# Main_System.net
KiCad netlist of a schematic drawn in Altium Designer
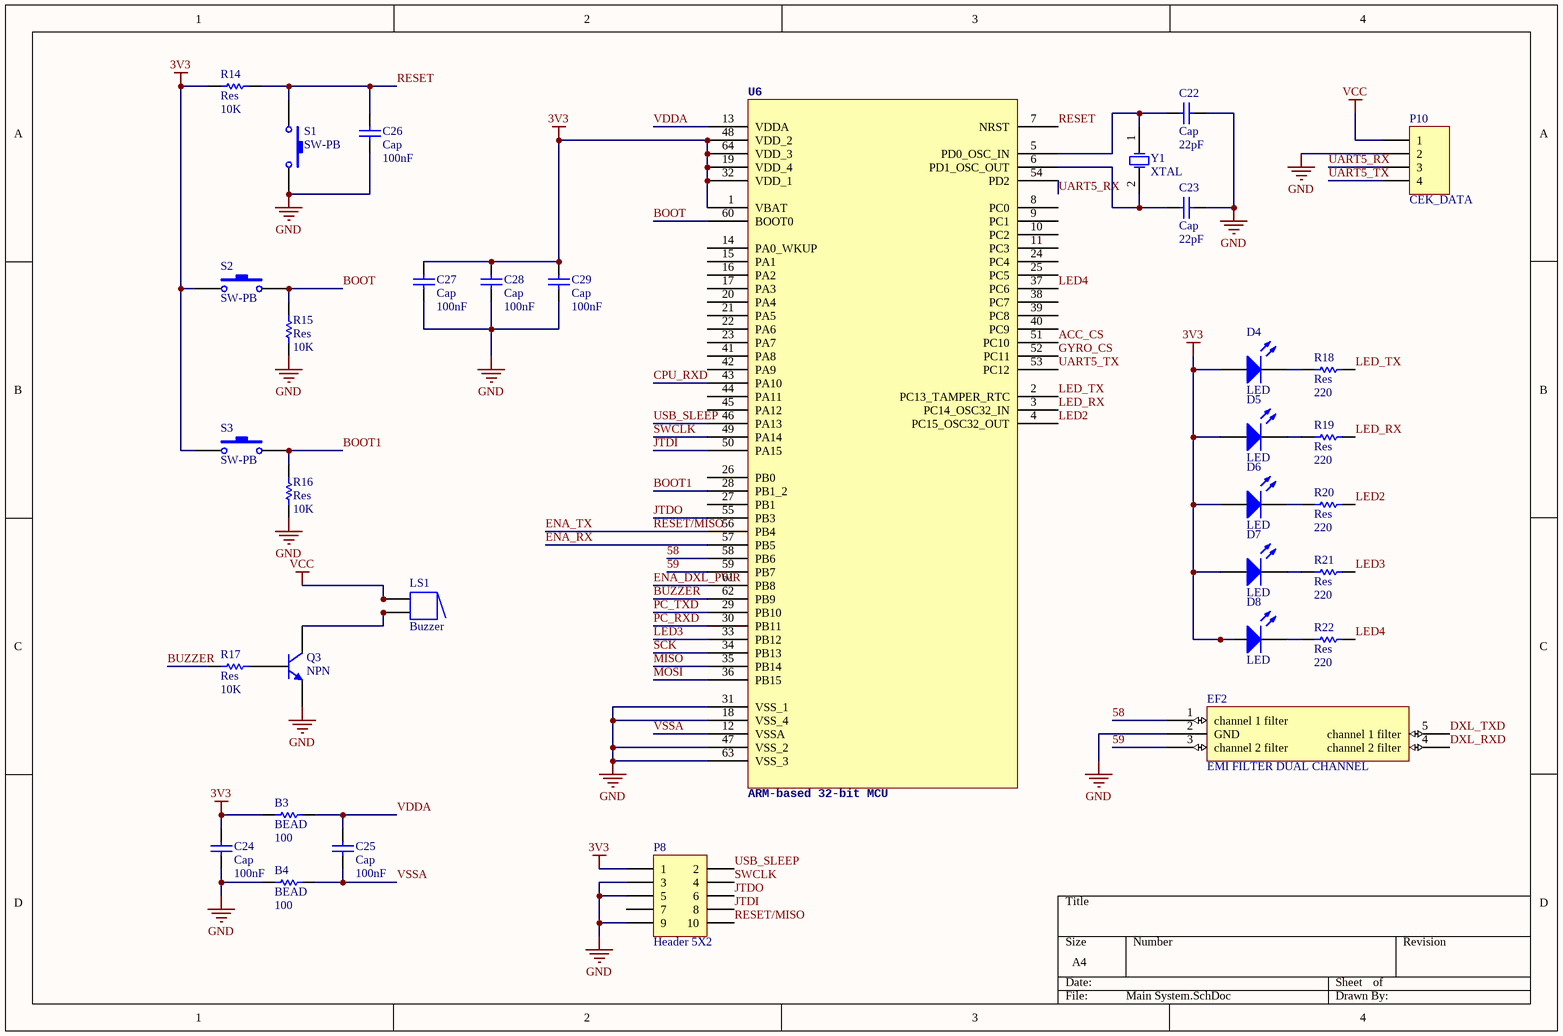
[diagram p0: Main System.SchDoc]

(export (version "E")
  (design (tool "Eeschema 10.0.6"))
  (components
    (comp (ref "B3")
      (value "BEAD")
      (footprint "0603-RES")
      (description "Resistor")
      (fields (field (name "ALTIUM_VALUE") "100") (field (name "PUBLISHER") "Altium Limited"))
      (libsource (lib "BarelangRobotics") (part "Res"))
    )
    (comp (ref "B4")
      (value "BEAD")
      (footprint "0603-RES")
      (description "Resistor")
      (fields (field (name "ALTIUM_VALUE") "100") (field (name "PUBLISHER") "Altium Limited"))
      (libsource (lib "BarelangRobotics") (part "Res"))
    )
    (comp (ref "C22")
      (value "Cap")
      (footprint "0603-CAP")
      (description "Capacitor")
      (fields (field (name "ALTIUM_VALUE") "22pF") (field (name "PUBLISHER") "Altium Limited"))
      (libsource (lib "BarelangRobotics") (part "Cap"))
    )
    (comp (ref "C23")
      (value "Cap")
      (footprint "0603-CAP")
      (description "Capacitor")
      (fields (field (name "ALTIUM_VALUE") "22pF") (field (name "PUBLISHER") "Altium Limited"))
      (libsource (lib "BarelangRobotics") (part "Cap"))
    )
    (comp (ref "C24")
      (value "Cap")
      (footprint "0603-CAP")
      (description "Capacitor")
      (fields (field (name "ALTIUM_VALUE") "100nF") (field (name "PUBLISHER") "Altium Limited"))
      (libsource (lib "BarelangRobotics") (part "Cap"))
    )
    (comp (ref "C25")
      (value "Cap")
      (footprint "0603-CAP")
      (description "Capacitor")
      (fields (field (name "ALTIUM_VALUE") "100nF") (field (name "PUBLISHER") "Altium Limited"))
      (libsource (lib "BarelangRobotics") (part "Cap"))
    )
    (comp (ref "C26")
      (value "Cap")
      (footprint "0603-CAP")
      (description "Capacitor")
      (fields (field (name "ALTIUM_VALUE") "100nF") (field (name "PUBLISHER") "Altium Limited"))
      (libsource (lib "BarelangRobotics") (part "Cap"))
    )
    (comp (ref "C27")
      (value "Cap")
      (footprint "0603-CAP")
      (description "Capacitor")
      (fields (field (name "ALTIUM_VALUE") "100nF") (field (name "PUBLISHER") "Altium Limited"))
      (libsource (lib "BarelangRobotics") (part "Cap"))
    )
    (comp (ref "C28")
      (value "Cap")
      (footprint "0603-CAP")
      (description "Capacitor")
      (fields (field (name "ALTIUM_VALUE") "100nF") (field (name "PUBLISHER") "Altium Limited"))
      (libsource (lib "BarelangRobotics") (part "Cap"))
    )
    (comp (ref "C29")
      (value "Cap")
      (footprint "0603-CAP")
      (description "Capacitor")
      (fields (field (name "ALTIUM_VALUE") "100nF") (field (name "PUBLISHER") "Altium Limited"))
      (libsource (lib "BarelangRobotics") (part "Cap"))
    )
    (comp (ref "D4")
      (value "LED")
      (footprint "CHIPLED_0603")
      (description "Typical INFRARED GaAs LED")
      (fields (field (name "PUBLISHER") "Altium Limited"))
      (libsource (lib "BarelangRobotics") (part "LED"))
    )
    (comp (ref "D5")
      (value "LED")
      (footprint "CHIPLED_0603")
      (description "Typical INFRARED GaAs LED")
      (fields (field (name "PUBLISHER") "Altium Limited"))
      (libsource (lib "BarelangRobotics") (part "LED"))
    )
    (comp (ref "D6")
      (value "LED")
      (footprint "CHIPLED_0603")
      (description "Typical INFRARED GaAs LED")
      (fields (field (name "PUBLISHER") "Altium Limited"))
      (libsource (lib "BarelangRobotics") (part "LED"))
    )
    (comp (ref "D7")
      (value "LED")
      (footprint "CHIPLED_0603")
      (description "Typical INFRARED GaAs LED")
      (fields (field (name "PUBLISHER") "Altium Limited"))
      (libsource (lib "BarelangRobotics") (part "LED"))
    )
    (comp (ref "D8")
      (value "LED")
      (footprint "CHIPLED_0603")
      (description "Typical INFRARED GaAs LED")
      (fields (field (name "PUBLISHER") "Altium Limited"))
      (libsource (lib "BarelangRobotics") (part "LED"))
    )
    (comp (ref "EF2")
      (value "EMI FILTER DUAL CHANNEL")
      (footprint "Emi Filter Dual Channel SOTFL")
      (libsource (lib "BRCM-Additional-Library") (part "EMI FILTER DUAL CHANNEL"))
    )
    (comp (ref "LS1")
      (value "Buzzer")
      (footprint "ABSM-1574")
      (description "Magnetic Transducer Buzzer")
      (fields (field (name "PUBLISHER") "Altium Limited"))
      (libsource (lib "Miscellaneous Devices") (part "Buzzer"))
    )
    (comp (ref "P8")
      (value "Header 5X2")
      (footprint "HDR2X5")
      (description "Header, 5-Pin, Dual row")
      (fields (field (name "PUBLISHER") "Altium Limited"))
      (libsource (lib "BarelangRobotics") (part "Header 5X2"))
    )
    (comp (ref "P10")
      (value "CEK_DATA")
      (footprint "HDR1X4")
      (description "Header, 4-Pin")
      (fields (field (name "PUBLISHER") "Altium Limited"))
      (libsource (lib "BarelangRobotics") (part "Header 4"))
    )
    (comp (ref "Q3")
      (value "NPN")
      (footprint "SOT23")
      (description "NPN Bipolar Transistor")
      (fields (field (name "PUBLISHER") "Altium Limited"))
      (libsource (lib "BarelangRobotics") (part "NPN"))
    )
    (comp (ref "R14")
      (value "Res")
      (footprint "0603-RES")
      (description "Resistor")
      (fields (field (name "ALTIUM_VALUE") "10K") (field (name "PUBLISHER") "Altium Limited"))
      (libsource (lib "BarelangRobotics") (part "Res"))
    )
    (comp (ref "R15")
      (value "Res")
      (footprint "0603-RES")
      (description "Resistor")
      (fields (field (name "ALTIUM_VALUE") "10K") (field (name "PUBLISHER") "Altium Limited"))
      (libsource (lib "BarelangRobotics") (part "Res"))
    )
    (comp (ref "R16")
      (value "Res")
      (footprint "0603-RES")
      (description "Resistor")
      (fields (field (name "ALTIUM_VALUE") "10K") (field (name "PUBLISHER") "Altium Limited"))
      (libsource (lib "BarelangRobotics") (part "Res"))
    )
    (comp (ref "R17")
      (value "Res")
      (footprint "0603-RES")
      (description "Resistor")
      (fields (field (name "ALTIUM_VALUE") "10K") (field (name "PUBLISHER") "Altium Limited"))
      (libsource (lib "BarelangRobotics") (part "Res"))
    )
    (comp (ref "R18")
      (value "Res")
      (footprint "0603-RES")
      (description "Resistor")
      (fields (field (name "ALTIUM_VALUE") "220") (field (name "PUBLISHER") "Altium Limited"))
      (libsource (lib "BarelangRobotics") (part "Res"))
    )
    (comp (ref "R19")
      (value "Res")
      (footprint "0603-RES")
      (description "Resistor")
      (fields (field (name "ALTIUM_VALUE") "220") (field (name "PUBLISHER") "Altium Limited"))
      (libsource (lib "BarelangRobotics") (part "Res"))
    )
    (comp (ref "R20")
      (value "Res")
      (footprint "0603-RES")
      (description "Resistor")
      (fields (field (name "ALTIUM_VALUE") "220") (field (name "PUBLISHER") "Altium Limited"))
      (libsource (lib "BarelangRobotics") (part "Res"))
    )
    (comp (ref "R21")
      (value "Res")
      (footprint "0603-RES")
      (description "Resistor")
      (fields (field (name "ALTIUM_VALUE") "220") (field (name "PUBLISHER") "Altium Limited"))
      (libsource (lib "BarelangRobotics") (part "Res"))
    )
    (comp (ref "R22")
      (value "Res")
      (footprint "0603-RES")
      (description "Resistor")
      (fields (field (name "ALTIUM_VALUE") "220") (field (name "PUBLISHER") "Altium Limited"))
      (libsource (lib "BarelangRobotics") (part "Res"))
    )
    (comp (ref "S1")
      (value "SW-PB")
      (footprint "TACTILE-SWITCH-SMD")
      (description "Switch")
      (fields (field (name "PUBLISHER") "Altium Limited"))
      (libsource (lib "BarelangRobotics") (part "SW-PB"))
    )
    (comp (ref "S2")
      (value "SW-PB")
      (footprint "TACTILE-SWITCH-SMD")
      (description "Switch")
      (fields (field (name "PUBLISHER") "Altium Limited"))
      (libsource (lib "BarelangRobotics") (part "SW-PB"))
    )
    (comp (ref "S3")
      (value "SW-PB")
      (footprint "TACTILE-SWITCH-SMD")
      (description "Switch")
      (fields (field (name "PUBLISHER") "Altium Limited"))
      (libsource (lib "BarelangRobotics") (part "SW-PB"))
    )
    (comp (ref "U6")
      (value "ARM-based 32-bit MCU")
      (footprint "QFP-64N")
      (fields (field (name "MPN") "STM32F103RET6"))
      (libsource (lib "BarelangRobotics") (part "STM32F103RET6"))
    )
    (comp (ref "Y1")
      (value "XTAL")
      (footprint "HC49US")
      (description "Crystal Oscillator")
      (fields (field (name "PUBLISHER") "Altium Limited"))
      (libsource (lib "BarelangRobotics") (part "XTAL"))
    )
  )
  (nets
    (net (code "1") (name "/58") (class "Default")
      (node (ref "EF2") (pin "1") (pinfunction "channel_1_filter_1") (pintype "bidirectional"))
      (node (ref "U6") (pin "58") (pinfunction "PB6_58") (pintype "passive"))
    )
    (net (code "2") (name "/59") (class "Default")
      (node (ref "EF2") (pin "3") (pinfunction "channel_2_filter_3") (pintype "bidirectional"))
      (node (ref "U6") (pin "59") (pinfunction "PB7_59") (pintype "passive"))
    )
    (net (code "3") (name "/ACC_CS") (class "Default")
      (node (ref "U6") (pin "51") (pinfunction "PC10_51") (pintype "passive"))
    )
    (net (code "4") (name "/BOOT") (class "Default")
      (node (ref "R15") (pin "2") (pinfunction "2_2") (pintype "passive"))
      (node (ref "S2") (pin "3") (pinfunction "3_3") (pintype "passive"))
      (node (ref "U6") (pin "60") (pinfunction "BOOT0_60") (pintype "passive"))
    )
    (net (code "5") (name "/BOOT1") (class "Default")
      (node (ref "R16") (pin "2") (pinfunction "2_2") (pintype "passive"))
      (node (ref "S3") (pin "3") (pinfunction "3_3") (pintype "passive"))
      (node (ref "U6") (pin "28") (pinfunction "PB1_2_28") (pintype "passive"))
    )
    (net (code "6") (name "/BUZZER") (class "Default")
      (node (ref "R17") (pin "2") (pinfunction "2_2") (pintype "passive"))
      (node (ref "U6") (pin "62") (pinfunction "PB9_62") (pintype "passive"))
    )
    (net (code "7") (name "/CPU_RXD") (class "Default")
      (node (ref "U6") (pin "43") (pinfunction "PA10_43") (pintype "passive"))
    )
    (net (code "8") (name "/DXL_RXD") (class "Default")
      (node (ref "EF2") (pin "4") (pinfunction "channel_2_filter_4") (pintype "bidirectional"))
    )
    (net (code "9") (name "/DXL_TXD") (class "Default")
      (node (ref "EF2") (pin "5") (pinfunction "channel_1_filter_5") (pintype "bidirectional"))
    )
    (net (code "10") (name "/ENA_DXL_PWR") (class "Default")
      (node (ref "U6") (pin "61") (pinfunction "PB8_61") (pintype "passive"))
    )
    (net (code "11") (name "/ENA_RX") (class "Default")
      (node (ref "U6") (pin "57") (pinfunction "PB5_57") (pintype "passive"))
    )
    (net (code "12") (name "/ENA_TX") (class "Default")
      (node (ref "P8") (pin "10") (pinfunction "10_10") (pintype "passive"))
      (node (ref "U6") (pin "56") (pinfunction "PB4_56") (pintype "passive"))
    )
    (net (code "13") (name "/GYRO_CS") (class "Default")
      (node (ref "U6") (pin "52") (pinfunction "PC11_52") (pintype "passive"))
    )
    (net (code "14") (name "/JTDI") (class "Default")
      (node (ref "P8") (pin "8") (pinfunction "8_8") (pintype "passive"))
      (node (ref "U6") (pin "50") (pinfunction "PA15_50") (pintype "passive"))
    )
    (net (code "15") (name "/JTDO") (class "Default")
      (node (ref "P8") (pin "6") (pinfunction "6_6") (pintype "passive"))
      (node (ref "U6") (pin "55") (pinfunction "PB3_55") (pintype "passive"))
    )
    (net (code "16") (name "/LED2") (class "Default")
      (node (ref "R20") (pin "1") (pinfunction "1_1") (pintype "passive"))
      (node (ref "U6") (pin "4") (pinfunction "PC15_OSC32_OUT_4") (pintype "passive"))
    )
    (net (code "17") (name "/LED3") (class "Default")
      (node (ref "R21") (pin "1") (pinfunction "1_1") (pintype "passive"))
      (node (ref "U6") (pin "33") (pinfunction "PB12_33") (pintype "passive"))
    )
    (net (code "18") (name "/LED4") (class "Default")
      (node (ref "R22") (pin "1") (pinfunction "1_1") (pintype "passive"))
      (node (ref "U6") (pin "37") (pinfunction "PC6_37") (pintype "passive"))
    )
    (net (code "19") (name "/LED_RX") (class "Default")
      (node (ref "R19") (pin "1") (pinfunction "1_1") (pintype "passive"))
      (node (ref "U6") (pin "3") (pinfunction "PC14_OSC32_IN_3") (pintype "passive"))
    )
    (net (code "20") (name "/LED_TX") (class "Default")
      (node (ref "R18") (pin "1") (pinfunction "1_1") (pintype "passive"))
      (node (ref "U6") (pin "2") (pinfunction "PC13_TAMPER_RTC_2") (pintype "passive"))
    )
    (net (code "21") (name "/MISO") (class "Default")
      (node (ref "U6") (pin "35") (pinfunction "PB14_35") (pintype "passive"))
    )
    (net (code "22") (name "/MOSI") (class "Default")
      (node (ref "U6") (pin "36") (pinfunction "PB15_36") (pintype "passive"))
    )
    (net (code "23") (name "/PC_RXD") (class "Default")
      (node (ref "U6") (pin "30") (pinfunction "PB11_30") (pintype "passive"))
    )
    (net (code "24") (name "/PC_TXD") (class "Default")
      (node (ref "U6") (pin "29") (pinfunction "PB10_29") (pintype "passive"))
    )
    (net (code "25") (name "/RESET") (class "Default")
      (node (ref "C26") (pin "2") (pinfunction "2_2") (pintype "passive"))
      (node (ref "R14") (pin "2") (pinfunction "2_2") (pintype "passive"))
      (node (ref "S1") (pin "1") (pinfunction "1_1") (pintype "passive"))
      (node (ref "U6") (pin "7") (pinfunction "NRST_7") (pintype "passive"))
    )
    (net (code "26") (name "/SCK") (class "Default")
      (node (ref "U6") (pin "34") (pinfunction "PB13_34") (pintype "passive"))
    )
    (net (code "27") (name "/SWCLK") (class "Default")
      (node (ref "P8") (pin "4") (pinfunction "4_4") (pintype "passive"))
      (node (ref "U6") (pin "49") (pinfunction "PA14_49") (pintype "passive"))
    )
    (net (code "28") (name "/UART5_RX") (class "Default")
      (node (ref "P10") (pin "3") (pinfunction "3_3") (pintype "passive"))
      (node (ref "U6") (pin "54") (pinfunction "PD2_54") (pintype "passive"))
    )
    (net (code "29") (name "/UART5_TX") (class "Default")
      (node (ref "P10") (pin "4") (pinfunction "4_4") (pintype "passive"))
      (node (ref "U6") (pin "53") (pinfunction "PC12_53") (pintype "passive"))
    )
    (net (code "30") (name "/USB_SLEEP") (class "Default")
      (node (ref "P8") (pin "2") (pinfunction "2_2") (pintype "passive"))
      (node (ref "U6") (pin "46") (pinfunction "PA13_46") (pintype "passive"))
    )
    (net (code "31") (name "/VDDA") (class "Default")
      (node (ref "B3") (pin "1") (pinfunction "1_1") (pintype "passive"))
      (node (ref "C25") (pin "2") (pinfunction "2_2") (pintype "passive"))
      (node (ref "U6") (pin "13") (pinfunction "VDDA_13") (pintype "passive"))
    )
    (net (code "32") (name "/VSSA") (class "Default")
      (node (ref "B4") (pin "1") (pinfunction "1_1") (pintype "passive"))
      (node (ref "C25") (pin "1") (pinfunction "1_1") (pintype "passive"))
      (node (ref "U6") (pin "12") (pinfunction "VSSA_12") (pintype "passive"))
    )
    (net (code "33") (name "3V3") (class "Default")
      (node (ref "B3") (pin "2") (pinfunction "2_2") (pintype "passive"))
      (node (ref "C24") (pin "2") (pinfunction "2_2") (pintype "passive"))
      (node (ref "C27") (pin "2") (pinfunction "2_2") (pintype "passive"))
      (node (ref "C28") (pin "2") (pinfunction "2_2") (pintype "passive"))
      (node (ref "C29") (pin "2") (pinfunction "2_2") (pintype "passive"))
      (node (ref "D4") (pin "1") (pinfunction "A_1") (pintype "passive"))
      (node (ref "D5") (pin "1") (pinfunction "A_1") (pintype "passive"))
      (node (ref "D6") (pin "1") (pinfunction "A_1") (pintype "passive"))
      (node (ref "D7") (pin "1") (pinfunction "A_1") (pintype "passive"))
      (node (ref "D8") (pin "1") (pinfunction "A_1") (pintype "passive"))
      (node (ref "P8") (pin "1") (pinfunction "1_1") (pintype "passive"))
      (node (ref "R14") (pin "1") (pinfunction "1_1") (pintype "passive"))
      (node (ref "S2") (pin "1") (pinfunction "1_1") (pintype "passive"))
      (node (ref "S3") (pin "1") (pinfunction "1_1") (pintype "passive"))
      (node (ref "U6") (pin "1") (pinfunction "VBAT_1") (pintype "passive"))
      (node (ref "U6") (pin "19") (pinfunction "VDD_4_19") (pintype "passive"))
      (node (ref "U6") (pin "32") (pinfunction "VDD_1_32") (pintype "passive"))
      (node (ref "U6") (pin "48") (pinfunction "VDD_2_48") (pintype "passive"))
      (node (ref "U6") (pin "64") (pinfunction "VDD_3_64") (pintype "passive"))
    )
    (net (code "34") (name "GND") (class "Default")
      (node (ref "B4") (pin "2") (pinfunction "2_2") (pintype "passive"))
      (node (ref "C22") (pin "2") (pinfunction "2_2") (pintype "passive"))
      (node (ref "C23") (pin "2") (pinfunction "2_2") (pintype "passive"))
      (node (ref "C24") (pin "1") (pinfunction "1_1") (pintype "passive"))
      (node (ref "C26") (pin "1") (pinfunction "1_1") (pintype "passive"))
      (node (ref "C27") (pin "1") (pinfunction "1_1") (pintype "passive"))
      (node (ref "C28") (pin "1") (pinfunction "1_1") (pintype "passive"))
      (node (ref "C29") (pin "1") (pinfunction "1_1") (pintype "passive"))
      (node (ref "EF2") (pin "2") (pinfunction "GND_2") (pintype "power_in"))
      (node (ref "P10") (pin "2") (pinfunction "2_2") (pintype "passive"))
      (node (ref "P8") (pin "3") (pinfunction "3_3") (pintype "passive"))
      (node (ref "P8") (pin "5") (pinfunction "5_5") (pintype "passive"))
      (node (ref "P8") (pin "9") (pinfunction "9_9") (pintype "passive"))
      (node (ref "Q3") (pin "2") (pinfunction "E_2") (pintype "passive"))
      (node (ref "R15") (pin "1") (pinfunction "1_1") (pintype "passive"))
      (node (ref "R16") (pin "1") (pinfunction "1_1") (pintype "passive"))
      (node (ref "S1") (pin "3") (pinfunction "3_3") (pintype "passive"))
      (node (ref "U6") (pin "18") (pinfunction "VSS_4_18") (pintype "passive"))
      (node (ref "U6") (pin "31") (pinfunction "VSS_1_31") (pintype "passive"))
      (node (ref "U6") (pin "47") (pinfunction "VSS_2_47") (pintype "passive"))
      (node (ref "U6") (pin "63") (pinfunction "VSS_3_63") (pintype "passive"))
    )
    (net (code "35") (name "Net-(D4-K)") (class "Default")
      (node (ref "D4") (pin "2") (pinfunction "K_2") (pintype "passive"))
      (node (ref "R18") (pin "2") (pinfunction "2_2") (pintype "passive"))
    )
    (net (code "36") (name "Net-(D5-K)") (class "Default")
      (node (ref "D5") (pin "2") (pinfunction "K_2") (pintype "passive"))
      (node (ref "R19") (pin "2") (pinfunction "2_2") (pintype "passive"))
    )
    (net (code "37") (name "Net-(D6-K)") (class "Default")
      (node (ref "D6") (pin "2") (pinfunction "K_2") (pintype "passive"))
      (node (ref "R20") (pin "2") (pinfunction "2_2") (pintype "passive"))
    )
    (net (code "38") (name "Net-(D7-K)") (class "Default")
      (node (ref "D7") (pin "2") (pinfunction "K_2") (pintype "passive"))
      (node (ref "R21") (pin "2") (pinfunction "2_2") (pintype "passive"))
    )
    (net (code "39") (name "Net-(D8-K)") (class "Default")
      (node (ref "D8") (pin "2") (pinfunction "K_2") (pintype "passive"))
      (node (ref "R22") (pin "2") (pinfunction "2_2") (pintype "passive"))
    )
    (net (code "40") (name "Net-(Q3-B)") (class "Default")
      (node (ref "Q3") (pin "1") (pinfunction "B_1") (pintype "passive"))
      (node (ref "R17") (pin "1") (pinfunction "1_1") (pintype "passive"))
    )
    (net (code "41") (name "Net-(Q3-C)") (class "Default")
      (node (ref "LS1") (pin "2") (pinfunction "2_2") (pintype "passive"))
      (node (ref "LS1") (pin "2A") (pinfunction "2A_2A") (pintype "passive"))
      (node (ref "Q3") (pin "3") (pinfunction "C_3") (pintype "passive"))
    )
    (net (code "42") (name "Net-(U6-PD0_OSC_IN)") (class "Default")
      (node (ref "C22") (pin "1") (pinfunction "1_1") (pintype "passive"))
      (node (ref "U6") (pin "5") (pinfunction "PD0_OSC_IN_5") (pintype "passive"))
      (node (ref "Y1") (pin "1") (pinfunction "OSC1_1") (pintype "passive"))
    )
    (net (code "43") (name "Net-(U6-PD1_OSC_OUT)") (class "Default")
      (node (ref "C23") (pin "1") (pinfunction "1_1") (pintype "passive"))
      (node (ref "U6") (pin "6") (pinfunction "PD1_OSC_OUT_6") (pintype "passive"))
      (node (ref "Y1") (pin "2") (pinfunction "OSC2_2") (pintype "passive"))
    )
    (net (code "44") (name "VCC") (class "Default")
      (node (ref "LS1") (pin "1") (pinfunction "1_1") (pintype "passive"))
      (node (ref "LS1") (pin "1A") (pinfunction "1A_1A") (pintype "passive"))
      (node (ref "P10") (pin "1") (pinfunction "1_1") (pintype "passive"))
    )
    (net (code "45") (name "unconnected-(P8-Pad7)") (class "Default")
      (node (ref "P8") (pin "7") (pinfunction "7_7") (pintype "passive"))
    )
    (net (code "46") (name "unconnected-(U6-PA0_WKUP-Pad14)") (class "Default")
      (node (ref "U6") (pin "14") (pinfunction "PA0_WKUP_14") (pintype "passive"))
    )
    (net (code "47") (name "unconnected-(U6-PA1-Pad15)") (class "Default")
      (node (ref "U6") (pin "15") (pinfunction "PA1_15") (pintype "passive"))
    )
    (net (code "48") (name "unconnected-(U6-PA2-Pad16)") (class "Default")
      (node (ref "U6") (pin "16") (pinfunction "PA2_16") (pintype "passive"))
    )
    (net (code "49") (name "unconnected-(U6-PA3-Pad17)") (class "Default")
      (node (ref "U6") (pin "17") (pinfunction "PA3_17") (pintype "passive"))
    )
    (net (code "50") (name "unconnected-(U6-PA4-Pad20)") (class "Default")
      (node (ref "U6") (pin "20") (pinfunction "PA4_20") (pintype "passive"))
    )
    (net (code "51") (name "unconnected-(U6-PA5-Pad21)") (class "Default")
      (node (ref "U6") (pin "21") (pinfunction "PA5_21") (pintype "passive"))
    )
    (net (code "52") (name "unconnected-(U6-PA6-Pad22)") (class "Default")
      (node (ref "U6") (pin "22") (pinfunction "PA6_22") (pintype "passive"))
    )
    (net (code "53") (name "unconnected-(U6-PA7-Pad23)") (class "Default")
      (node (ref "U6") (pin "23") (pinfunction "PA7_23") (pintype "passive"))
    )
    (net (code "54") (name "unconnected-(U6-PA8-Pad41)") (class "Default")
      (node (ref "U6") (pin "41") (pinfunction "PA8_41") (pintype "passive"))
    )
    (net (code "55") (name "unconnected-(U6-PA9-Pad42)") (class "Default")
      (node (ref "U6") (pin "42") (pinfunction "PA9_42") (pintype "passive"))
    )
    (net (code "56") (name "unconnected-(U6-PA11-Pad44)") (class "Default")
      (node (ref "U6") (pin "44") (pinfunction "PA11_44") (pintype "passive"))
    )
    (net (code "57") (name "unconnected-(U6-PA12-Pad45)") (class "Default")
      (node (ref "U6") (pin "45") (pinfunction "PA12_45") (pintype "passive"))
    )
    (net (code "58") (name "unconnected-(U6-PB0-Pad26)") (class "Default")
      (node (ref "U6") (pin "26") (pinfunction "PB0_26") (pintype "passive"))
    )
    (net (code "59") (name "unconnected-(U6-PB1-Pad27)") (class "Default")
      (node (ref "U6") (pin "27") (pinfunction "PB1_27") (pintype "passive"))
    )
    (net (code "60") (name "unconnected-(U6-PC0-Pad8)") (class "Default")
      (node (ref "U6") (pin "8") (pinfunction "PC0_8") (pintype "passive"))
    )
    (net (code "61") (name "unconnected-(U6-PC1-Pad9)") (class "Default")
      (node (ref "U6") (pin "9") (pinfunction "PC1_9") (pintype "passive"))
    )
    (net (code "62") (name "unconnected-(U6-PC2-Pad10)") (class "Default")
      (node (ref "U6") (pin "10") (pinfunction "PC2_10") (pintype "passive"))
    )
    (net (code "63") (name "unconnected-(U6-PC3-Pad11)") (class "Default")
      (node (ref "U6") (pin "11") (pinfunction "PC3_11") (pintype "passive"))
    )
    (net (code "64") (name "unconnected-(U6-PC4-Pad24)") (class "Default")
      (node (ref "U6") (pin "24") (pinfunction "PC4_24") (pintype "passive"))
    )
    (net (code "65") (name "unconnected-(U6-PC5-Pad25)") (class "Default")
      (node (ref "U6") (pin "25") (pinfunction "PC5_25") (pintype "passive"))
    )
    (net (code "66") (name "unconnected-(U6-PC7-Pad38)") (class "Default")
      (node (ref "U6") (pin "38") (pinfunction "PC7_38") (pintype "passive"))
    )
    (net (code "67") (name "unconnected-(U6-PC8-Pad39)") (class "Default")
      (node (ref "U6") (pin "39") (pinfunction "PC8_39") (pintype "passive"))
    )
    (net (code "68") (name "unconnected-(U6-PC9-Pad40)") (class "Default")
      (node (ref "U6") (pin "40") (pinfunction "PC9_40") (pintype "passive"))
    )
  )
)
